# SMC_FrontPanel_ExtensionBoard_Step2_V12_.net
KiCad netlist of a schematic drawn in EAGLE
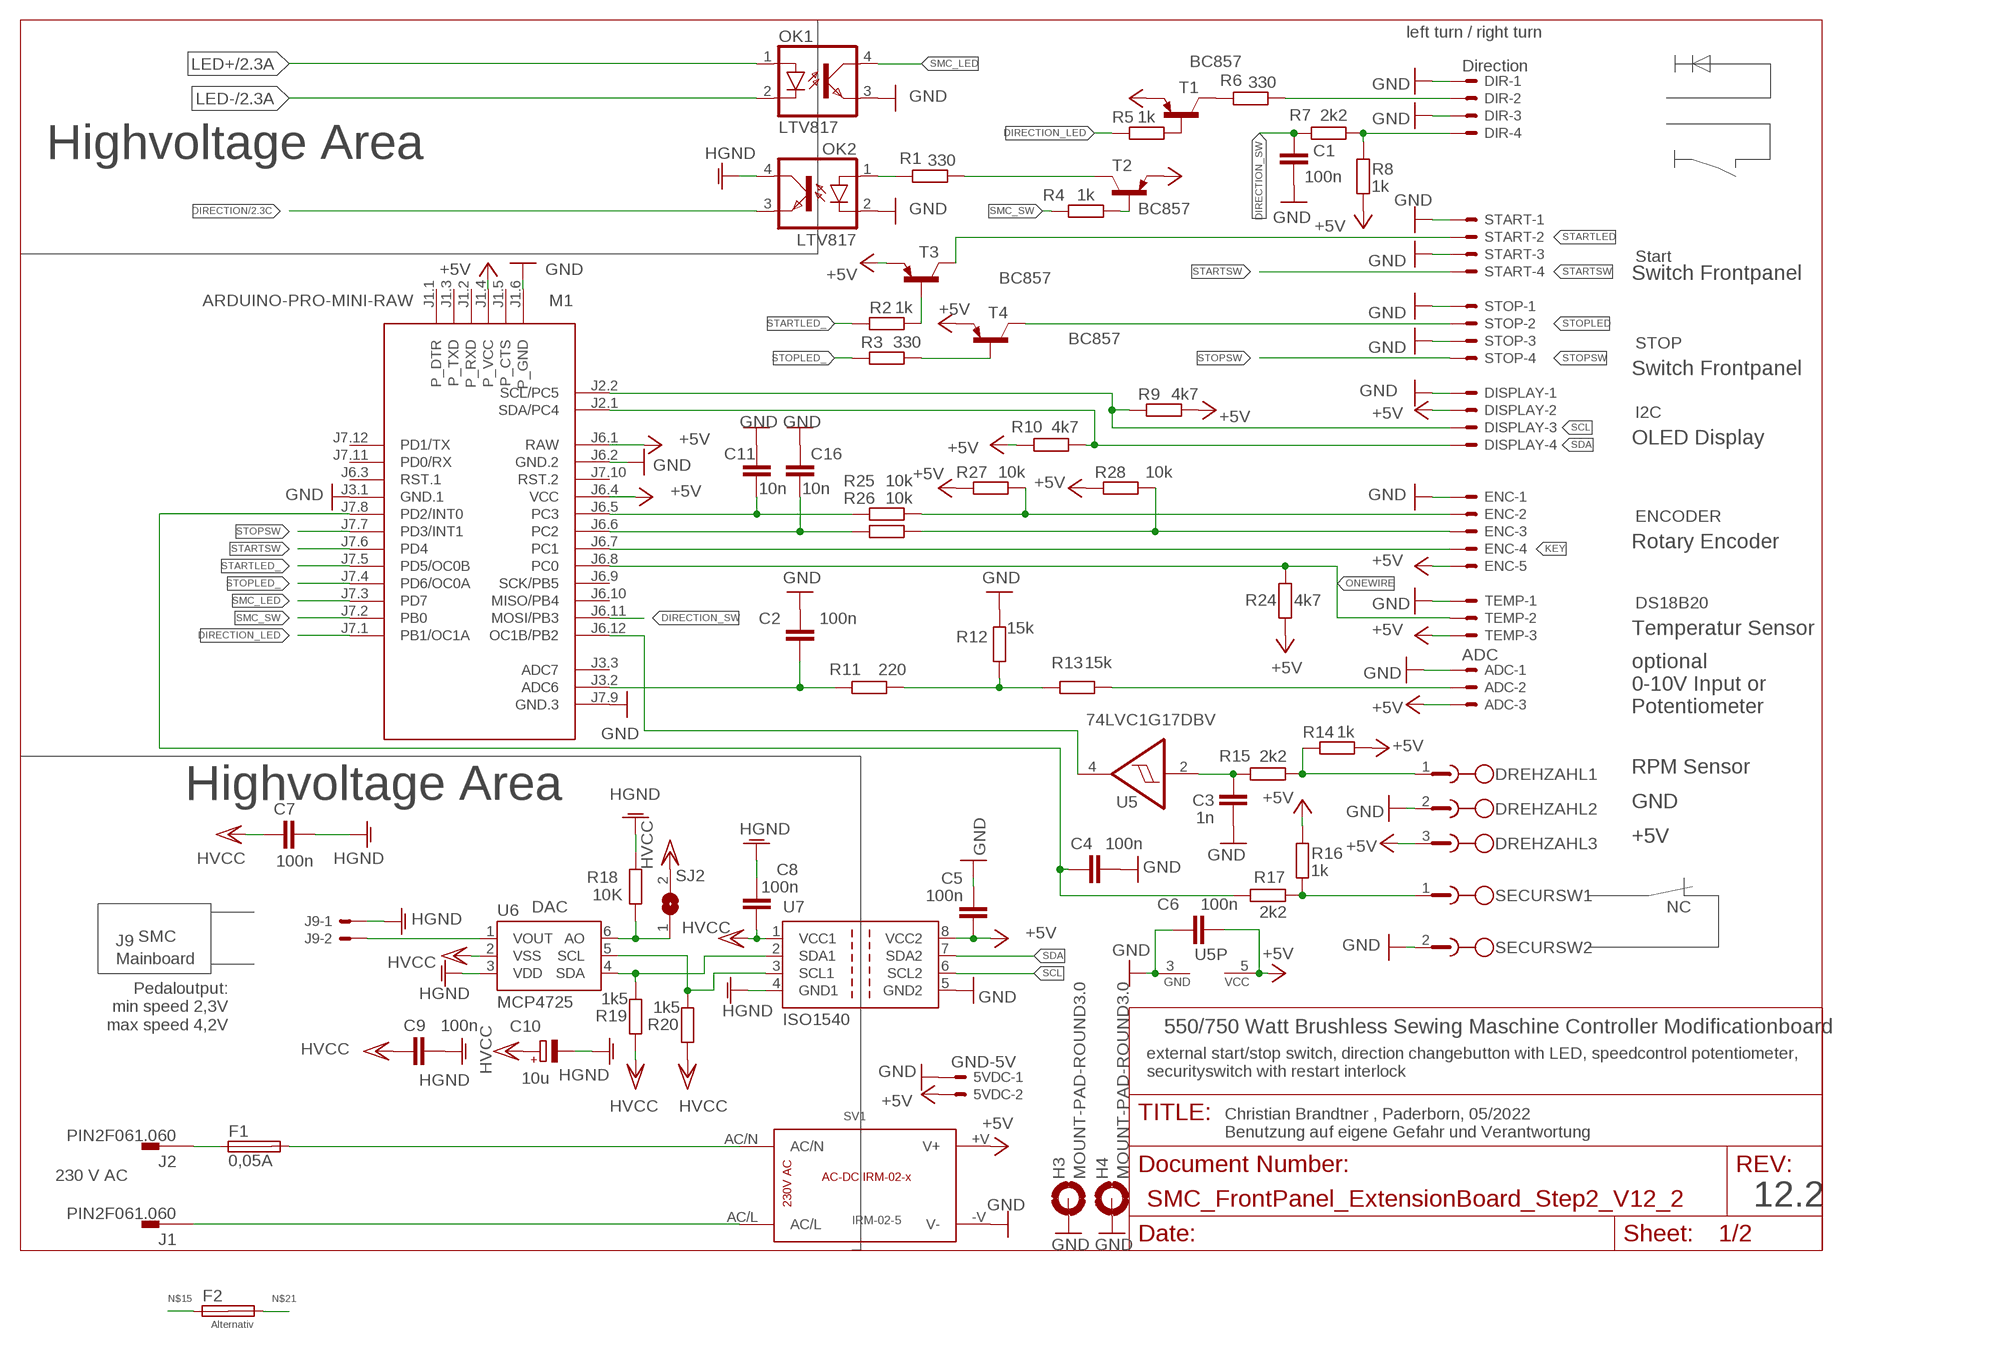
[diagram p0: schematic, sheet 1]
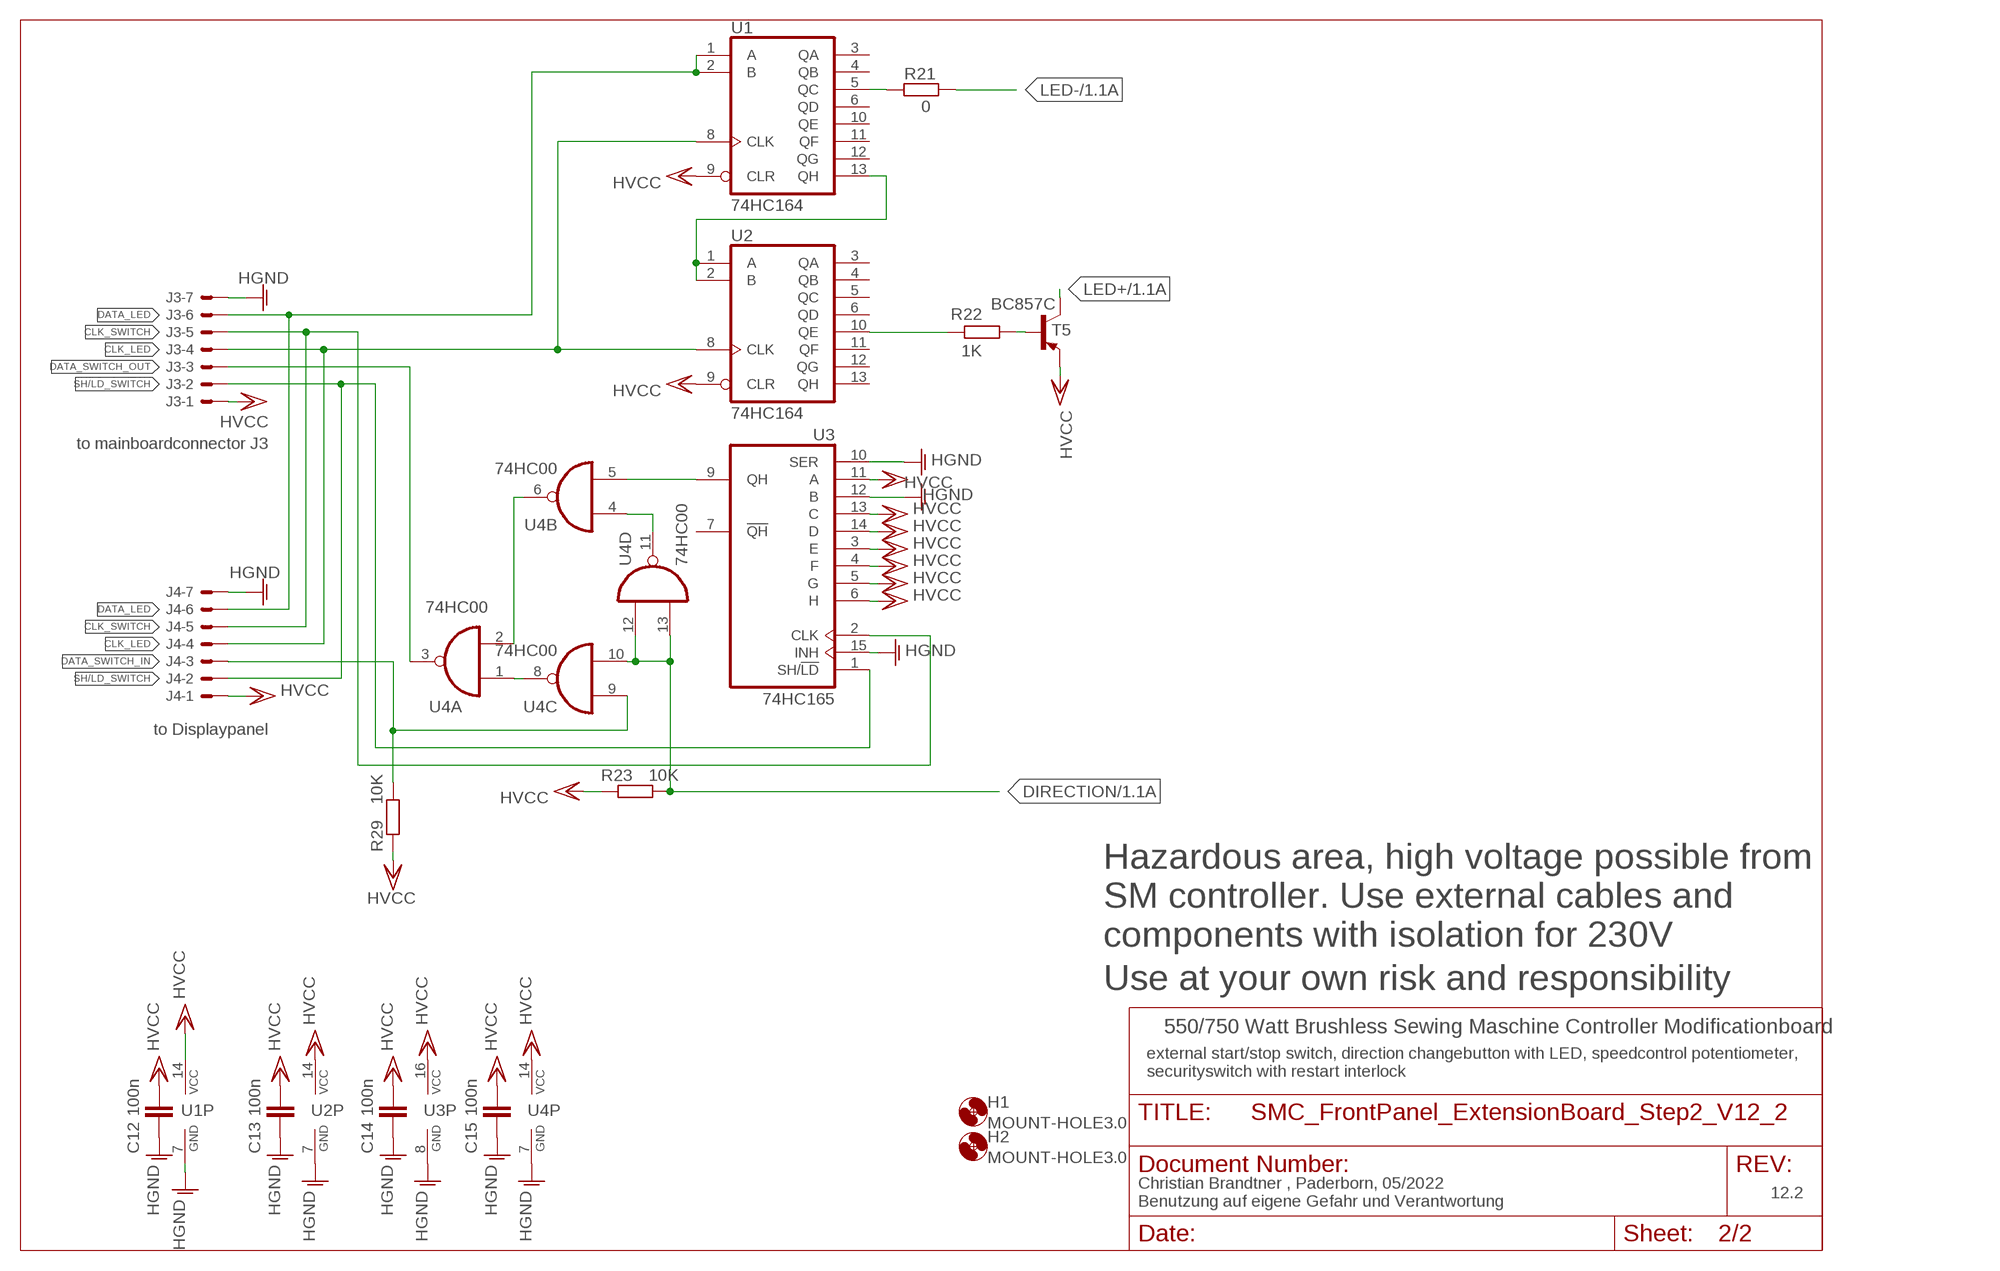
[diagram p1: schematic, sheet 2]

(export (version "E")
  (design (tool "Eeschema 10.0.6"))
  (components
    (comp (ref "C12")
      (value "100n")
      (footprint "eagle-import:C0805")
      (libsource (lib "eagle-import") (part "C-EUC0805"))
    )
    (comp (ref "C13")
      (value "100n")
      (footprint "eagle-import:C0805")
      (libsource (lib "eagle-import") (part "C-EUC0805"))
    )
    (comp (ref "C14")
      (value "100n")
      (footprint "eagle-import:C0805")
      (libsource (lib "eagle-import") (part "C-EUC0805"))
    )
    (comp (ref "C15")
      (value "100n")
      (footprint "eagle-import:C0805")
      (libsource (lib "eagle-import") (part "C-EUC0805"))
    )
    (comp (ref "H1")
      (value "MOUNT-HOLE3.0")
      (footprint "eagle-import:3,0")
      (libsource (lib "eagle-import") (part "MOUNT-HOLE3.0"))
    )
    (comp (ref "H2")
      (value "MOUNT-HOLE3.0")
      (footprint "eagle-import:3,0")
      (libsource (lib "eagle-import") (part "MOUNT-HOLE3.0"))
    )
    (comp (ref "J3")
      (value "to mainboardconnector J3")
      (footprint "eagle-import:JST-XH-07-PACKAGE-ROUND-PAD")
      (libsource (lib "eagle-import") (part "JST-XH-07-PIN-ROUND-PAD"))
    )
    (comp (ref "J4")
      (value "to Displaypanel")
      (footprint "eagle-import:JST-XH-07-PACKAGE-ROUND-PAD")
      (libsource (lib "eagle-import") (part "JST-XH-07-PIN-ROUND-PAD"))
    )
    (comp (ref "R21")
      (value "0")
      (footprint "eagle-import:R0805")
      (libsource (lib "eagle-import") (part "R-EU_R0805"))
    )
    (comp (ref "R22")
      (value "1K")
      (footprint "eagle-import:R0805")
      (libsource (lib "eagle-import") (part "R-EU_R0805"))
    )
    (comp (ref "R23")
      (value "10K")
      (footprint "eagle-import:R0805")
      (libsource (lib "eagle-import") (part "R-EU_R0805"))
    )
    (comp (ref "R29")
      (value "10K")
      (footprint "eagle-import:R0805")
      (libsource (lib "eagle-import") (part "R-EU_R0805"))
    )
    (comp (ref "T5")
      (value "BC857C")
      (footprint "eagle-import:SOT23-BEC")
      (libsource (lib "eagle-import") (part "-PNP-SOT23-BECBC857C"))
    )
    (comp (ref "U1")
      (value "74HC164")
      (footprint "eagle-import:SO14")
      (libsource (lib "eagle-import") (part "74164DHC"))
    )
    (comp (ref "U2")
      (value "74HC164")
      (footprint "eagle-import:SO14")
      (libsource (lib "eagle-import") (part "74164DHC"))
    )
    (comp (ref "U3")
      (value "74HC165")
      (footprint "eagle-import:SO16")
      (libsource (lib "eagle-import") (part "74165DHC"))
    )
    (comp (ref "U4")
      (value "74HC00")
      (footprint "eagle-import:SO14")
      (libsource (lib "eagle-import") (part "7400DHC"))
    )
    (comp (ref "5VDC")
      (value "GND-5V")
      (footprint "eagle-import:JST-XH-02-PACKAGE-ROUND-PAD")
      (libsource (lib "eagle-import") (part "JST-XH-02-PIN-ROUND-PAD"))
    )
    (comp (ref "ADC")
      (value "ADC")
      (footprint "eagle-import:JST-XH-03-PACKAGE-ROUND-PAD")
      (libsource (lib "eagle-import") (part "JST-XH-03-PIN-ROUND-PAD"))
    )
    (comp (ref "C1")
      (value "100n")
      (footprint "eagle-import:C0805")
      (libsource (lib "eagle-import") (part "C-EUC0805"))
    )
    (comp (ref "C2")
      (value "100n")
      (footprint "eagle-import:C0805")
      (libsource (lib "eagle-import") (part "C-EUC0805"))
    )
    (comp (ref "C3")
      (value "1n")
      (footprint "eagle-import:C0805")
      (libsource (lib "eagle-import") (part "C-EUC0805"))
    )
    (comp (ref "C4")
      (value "100n")
      (footprint "eagle-import:C0805")
      (libsource (lib "eagle-import") (part "C-EUC0805"))
    )
    (comp (ref "C5")
      (value "100n")
      (footprint "eagle-import:C0805")
      (libsource (lib "eagle-import") (part "C-EUC0805"))
    )
    (comp (ref "C6")
      (value "100n")
      (footprint "eagle-import:C0805")
      (libsource (lib "eagle-import") (part "C-EUC0805"))
    )
    (comp (ref "C7")
      (value "100n")
      (footprint "eagle-import:C0805")
      (libsource (lib "eagle-import") (part "C-EUC0805"))
    )
    (comp (ref "C8")
      (value "100n")
      (footprint "eagle-import:C0805")
      (libsource (lib "eagle-import") (part "C-EUC0805"))
    )
    (comp (ref "C9")
      (value "100n")
      (footprint "eagle-import:C0805")
      (libsource (lib "eagle-import") (part "C-EUC0805"))
    )
    (comp (ref "C10")
      (value "10u")
      (footprint "eagle-import:153CLV-0405")
      (libsource (lib "eagle-import") (part "CPOL-EU153CLV-0405"))
    )
    (comp (ref "C11")
      (value "10n")
      (footprint "eagle-import:C0805")
      (libsource (lib "eagle-import") (part "C-EUC0805"))
    )
    (comp (ref "C16")
      (value "10n")
      (footprint "eagle-import:C0805")
      (libsource (lib "eagle-import") (part "C-EUC0805"))
    )
    (comp (ref "DIR")
      (value "Direction")
      (footprint "eagle-import:JST-XH-04-PACKAGE-ROUND-PAD")
      (libsource (lib "eagle-import") (part "JST-XH-04-PIN-ROUND-PAD"))
    )
    (comp (ref "DISPLAY")
      (value "I2C")
      (footprint "eagle-import:JST-XH-04-PACKAGE-ROUND-PAD")
      (libsource (lib "eagle-import") (part "JST-XH-04-PIN-ROUND-PAD"))
    )
    (comp (ref "DREHZAHL")
      (value "MCV_1.5/3/-G-3.5")
      (footprint "eagle-import:1843619")
      (libsource (lib "eagle-import") (part "MCV_1.5/3/-G-3.5"))
    )
    (comp (ref "ENC")
      (value "ENCODER")
      (footprint "eagle-import:JST-XH-05-PACKAGE-ROUND-PAD")
      (libsource (lib "eagle-import") (part "JST-XH-05-PIN-ROUND-PAD"))
    )
    (comp (ref "F1")
      (value "0,05A")
      (footprint "eagle-import:MTA501100")
      (libsource (lib "eagle-import") (part "FUSE"))
    )
    (comp (ref "F2")
      (value "SHK20L")
      (footprint "eagle-import:SHK20L")
      (libsource (lib "eagle-import") (part "SHK20L"))
    )
    (comp (ref "H3")
      (value "MOUNT-PAD-ROUND3.0")
      (footprint "eagle-import:3,0-PAD")
      (libsource (lib "eagle-import") (part "MOUNT-PAD-ROUND3.0"))
    )
    (comp (ref "H4")
      (value "MOUNT-PAD-ROUND3.0")
      (footprint "eagle-import:3,0-PAD")
      (libsource (lib "eagle-import") (part "MOUNT-PAD-ROUND3.0"))
    )
    (comp (ref "J1")
      (value "PIN2F061.060")
      (footprint "eagle-import:F061.060")
      (libsource (lib "eagle-import") (part "PIN2F061.060"))
    )
    (comp (ref "J2")
      (value "PIN2F061.060")
      (footprint "eagle-import:F061.060")
      (libsource (lib "eagle-import") (part "PIN2F061.060"))
    )
    (comp (ref "J9")
      (value "JST-XH-02-PIN-ROUND-PAD")
      (footprint "eagle-import:JST-XH-02-PACKAGE-ROUND-PAD")
      (libsource (lib "eagle-import") (part "JST-XH-02-PIN-ROUND-PAD"))
    )
    (comp (ref "M1")
      (value "ARDUINO-PRO-MINI-RAW")
      (footprint "eagle-import:ARDUINO-PRO-MINI")
      (libsource (lib "eagle-import") (part "ARDUINO-PRO-MINI-RAW"))
    )
    (comp (ref "OK1")
      (value "LTV817")
      (footprint "eagle-import:SMD4-7")
      (fields (field (name "MF") "VISHAY/TELEFUNKEN") (field (name "MPN") "SFH6186-2"))
      (libsource (lib "eagle-import") (part "SFH618?6-2"))
    )
    (comp (ref "OK2")
      (value "LTV817")
      (footprint "eagle-import:SMD4-7")
      (fields (field (name "MF") "VISHAY/TELEFUNKEN") (field (name "MPN") "SFH6186-2"))
      (libsource (lib "eagle-import") (part "SFH618?6-2"))
    )
    (comp (ref "R1")
      (value "330")
      (footprint "eagle-import:R0805")
      (libsource (lib "eagle-import") (part "R-EU_R0805"))
    )
    (comp (ref "R2")
      (value "1k")
      (footprint "eagle-import:R0805")
      (libsource (lib "eagle-import") (part "R-EU_R0805"))
    )
    (comp (ref "R3")
      (value "330")
      (footprint "eagle-import:R0805")
      (libsource (lib "eagle-import") (part "R-EU_R0805"))
    )
    (comp (ref "R4")
      (value "1k")
      (footprint "eagle-import:R0805")
      (libsource (lib "eagle-import") (part "R-EU_R0805"))
    )
    (comp (ref "R5")
      (value "1k")
      (footprint "eagle-import:R0805")
      (libsource (lib "eagle-import") (part "R-EU_R0805"))
    )
    (comp (ref "R6")
      (value "330")
      (footprint "eagle-import:R0805")
      (libsource (lib "eagle-import") (part "R-EU_R0805"))
    )
    (comp (ref "R7")
      (value "2k2")
      (footprint "eagle-import:R0805")
      (libsource (lib "eagle-import") (part "R-EU_R0805"))
    )
    (comp (ref "R8")
      (value "1k")
      (footprint "eagle-import:R0805")
      (libsource (lib "eagle-import") (part "R-EU_R0805"))
    )
    (comp (ref "R9")
      (value "4k7")
      (footprint "eagle-import:R0805")
      (libsource (lib "eagle-import") (part "R-EU_R0805"))
    )
    (comp (ref "R10")
      (value "4k7")
      (footprint "eagle-import:R0805")
      (libsource (lib "eagle-import") (part "R-EU_R0805"))
    )
    (comp (ref "R11")
      (value "220")
      (footprint "eagle-import:R0805")
      (libsource (lib "eagle-import") (part "R-EU_R0805"))
    )
    (comp (ref "R12")
      (value "15k")
      (footprint "eagle-import:R0805")
      (libsource (lib "eagle-import") (part "R-EU_R0805"))
    )
    (comp (ref "R13")
      (value "15k")
      (footprint "eagle-import:R0805")
      (libsource (lib "eagle-import") (part "R-EU_R0805"))
    )
    (comp (ref "R14")
      (value "1k")
      (footprint "eagle-import:R0805")
      (libsource (lib "eagle-import") (part "R-EU_R0805"))
    )
    (comp (ref "R15")
      (value "2k2")
      (footprint "eagle-import:R0805")
      (libsource (lib "eagle-import") (part "R-EU_R0805"))
    )
    (comp (ref "R16")
      (value "1k")
      (footprint "eagle-import:R0805")
      (libsource (lib "eagle-import") (part "R-EU_R0805"))
    )
    (comp (ref "R17")
      (value "2k2")
      (footprint "eagle-import:R0805")
      (libsource (lib "eagle-import") (part "R-EU_R0805"))
    )
    (comp (ref "R18")
      (value "10K")
      (footprint "eagle-import:R0805")
      (libsource (lib "eagle-import") (part "R-EU_R0805"))
    )
    (comp (ref "R19")
      (value "1k5")
      (footprint "eagle-import:R0805")
      (libsource (lib "eagle-import") (part "R-EU_R0805"))
    )
    (comp (ref "R20")
      (value "1k5")
      (footprint "eagle-import:R0805")
      (libsource (lib "eagle-import") (part "R-EU_R0805"))
    )
    (comp (ref "R24")
      (value "4k7")
      (footprint "eagle-import:R0805")
      (libsource (lib "eagle-import") (part "R-EU_R0805"))
    )
    (comp (ref "R25")
      (value "10k")
      (footprint "eagle-import:R0805")
      (libsource (lib "eagle-import") (part "R-EU_R0805"))
    )
    (comp (ref "R26")
      (value "10k")
      (footprint "eagle-import:R0805")
      (libsource (lib "eagle-import") (part "R-EU_R0805"))
    )
    (comp (ref "R27")
      (value "10k")
      (footprint "eagle-import:R0805")
      (libsource (lib "eagle-import") (part "R-EU_R0805"))
    )
    (comp (ref "R28")
      (value "10k")
      (footprint "eagle-import:R0805")
      (libsource (lib "eagle-import") (part "R-EU_R0805"))
    )
    (comp (ref "SECURSW")
      (value "MCV_1,5/2-G-3,5")
      (footprint "eagle-import:1843606")
      (libsource (lib "eagle-import") (part "MCV_1,5/2-G-3,5"))
    )
    (comp (ref "SJ2") (value "SJ") (footprint "eagle-import:SJ") (libsource (lib "eagle-import") (part "SJ")))
    (comp (ref "START")
      (value "Start")
      (footprint "eagle-import:JST-XH-04-PACKAGE-ROUND-PAD")
      (libsource (lib "eagle-import") (part "JST-XH-04-PIN-ROUND-PAD"))
    )
    (comp (ref "STOP")
      (value "STOP")
      (footprint "eagle-import:JST-XH-04-PACKAGE-ROUND-PAD")
      (libsource (lib "eagle-import") (part "JST-XH-04-PIN-ROUND-PAD"))
    )
    (comp (ref "SV1")
      (value "IRM-02-5")
      (footprint "eagle-import:IRM-02-X")
      (libsource (lib "eagle-import") (part "IRM-02-X"))
    )
    (comp (ref "T1")
      (value "BC857")
      (footprint "eagle-import:SOT23-BEC")
      (libsource (lib "eagle-import") (part "BC857SMDA"))
    )
    (comp (ref "T2")
      (value "BC857")
      (footprint "eagle-import:SOT23-BEC")
      (libsource (lib "eagle-import") (part "BC857SMDA"))
    )
    (comp (ref "T3")
      (value "BC857")
      (footprint "eagle-import:SOT23-BEC")
      (libsource (lib "eagle-import") (part "BC857SMDA"))
    )
    (comp (ref "T4")
      (value "BC857")
      (footprint "eagle-import:SOT23-BEC")
      (libsource (lib "eagle-import") (part "BC857SMDA"))
    )
    (comp (ref "TEMP")
      (value "DS18B20")
      (footprint "eagle-import:JST-XH-03-PACKAGE-ROUND-PAD")
      (libsource (lib "eagle-import") (part "JST-XH-03-PIN-ROUND-PAD"))
    )
    (comp (ref "U5")
      (value "74LVC1G17DBV")
      (footprint "eagle-import:SOT23-5")
      (libsource (lib "eagle-import") (part "741G17DBVLVC"))
    )
    (comp (ref "U6")
      (value "MCP4725")
      (footprint "eagle-import:SOT23-6")
      (libsource (lib "eagle-import") (part "MCP4725SOT-23"))
    )
    (comp (ref "U7")
      (value "ISO1540")
      (footprint "eagle-import:SO-08")
      (libsource (lib "eagle-import") (part "ISO1540"))
    )
  )
  (nets
    (net (code "1") (name "+5V") (class "Default")
      (node (ref "5VDC") (pin "2") (pinfunction "S_2") (pintype "passive"))
      (node (ref "ADC") (pin "3") (pinfunction "S_3") (pintype "passive"))
      (node (ref "C5") (pin "1") (pinfunction "1_1") (pintype "passive"))
      (node (ref "C6") (pin "1") (pinfunction "1_1") (pintype "passive"))
      (node (ref "DISPLAY") (pin "2") (pinfunction "S_2") (pintype "passive"))
      (node (ref "DREHZAHL") (pin "3") (pinfunction "1_3") (pintype "passive"))
      (node (ref "ENC") (pin "5") (pinfunction "S_5") (pintype "passive"))
      (node (ref "M1") (pin "J1.4") (pinfunction "P_VCC_J1.4") (pintype "bidirectional"))
      (node (ref "M1") (pin "J6.1") (pinfunction "RAW_J6.1") (pintype "power_in"))
      (node (ref "M1") (pin "J6.4") (pinfunction "VCC_J6.4") (pintype "power_in"))
      (node (ref "R10") (pin "1") (pinfunction "1_1") (pintype "passive"))
      (node (ref "R14") (pin "1") (pinfunction "1_1") (pintype "passive"))
      (node (ref "R16") (pin "1") (pinfunction "1_1") (pintype "passive"))
      (node (ref "R24") (pin "2") (pinfunction "2_2") (pintype "passive"))
      (node (ref "R27") (pin "1") (pinfunction "1_1") (pintype "passive"))
      (node (ref "R28") (pin "1") (pinfunction "1_1") (pintype "passive"))
      (node (ref "R8") (pin "2") (pinfunction "2_2") (pintype "passive"))
      (node (ref "R9") (pin "1") (pinfunction "1_1") (pintype "passive"))
      (node (ref "SV1") (pin "+V") (pinfunction "V+_+V") (pintype "bidirectional"))
      (node (ref "T1") (pin "E") (pinfunction "E_E") (pintype "passive"))
      (node (ref "T2") (pin "E") (pinfunction "E_E") (pintype "passive"))
      (node (ref "T3") (pin "E") (pinfunction "E_E") (pintype "passive"))
      (node (ref "T4") (pin "E") (pinfunction "E_E") (pintype "passive"))
      (node (ref "TEMP") (pin "3") (pinfunction "S_3") (pintype "passive"))
      (node (ref "U5") (pin "5") (pinfunction "VCC_5") (pintype "power_in"))
      (node (ref "U7") (pin "8") (pinfunction "VCC2_8") (pintype "power_in"))
    )
    (net (code "2") (name "CLK_LED") (class "Default")
      (node (ref "J3") (pin "4") (pinfunction "S_4") (pintype "passive"))
      (node (ref "J4") (pin "4") (pinfunction "S_4") (pintype "passive"))
      (node (ref "U1") (pin "8") (pinfunction "CLK_8") (pintype "input"))
      (node (ref "U2") (pin "8") (pinfunction "CLK_8") (pintype "input"))
    )
    (net (code "3") (name "CLK_SWITCH") (class "Default")
      (node (ref "J3") (pin "5") (pinfunction "S_5") (pintype "passive"))
      (node (ref "J4") (pin "5") (pinfunction "S_5") (pintype "passive"))
      (node (ref "U3") (pin "2") (pinfunction "CLK_2") (pintype "input"))
    )
    (net (code "4") (name "DATA_LED") (class "Default")
      (node (ref "J3") (pin "6") (pinfunction "S_6") (pintype "passive"))
      (node (ref "J4") (pin "6") (pinfunction "S_6") (pintype "passive"))
      (node (ref "U1") (pin "1") (pinfunction "A_1") (pintype "input"))
      (node (ref "U1") (pin "2") (pinfunction "B_2") (pintype "input"))
    )
    (net (code "5") (name "DATA_SWITCH_IN") (class "Default")
      (node (ref "J4") (pin "3") (pinfunction "S_3") (pintype "passive"))
      (node (ref "R29") (pin "1") (pinfunction "1_1") (pintype "passive"))
      (node (ref "U4") (pin "9") (pinfunction "I0_9") (pintype "input"))
    )
    (net (code "6") (name "DATA_SWITCH_OUT") (class "Default")
      (node (ref "J3") (pin "3") (pinfunction "S_3") (pintype "passive"))
      (node (ref "U4") (pin "3") (pinfunction "O_3") (pintype "output"))
    )
    (net (code "7") (name "DIRECTION") (class "Default")
      (node (ref "OK2") (pin "3") (pinfunction "EMIT_3") (pintype "passive"))
      (node (ref "R23") (pin "1") (pinfunction "1_1") (pintype "passive"))
      (node (ref "U4") (pin "10") (pinfunction "I1_10") (pintype "input"))
      (node (ref "U4") (pin "12") (pinfunction "I0_12") (pintype "input"))
      (node (ref "U4") (pin "13") (pinfunction "I1_13") (pintype "input"))
    )
    (net (code "8") (name "DIRECTION_LED") (class "Default")
      (node (ref "M1") (pin "J7.1") (pinfunction "PB1/OC1A_J7.1") (pintype "bidirectional"))
      (node (ref "R5") (pin "2") (pinfunction "2_2") (pintype "passive"))
    )
    (net (code "9") (name "DIRECTION_SW") (class "Default")
      (node (ref "C1") (pin "2") (pinfunction "2_2") (pintype "passive"))
      (node (ref "M1") (pin "J6.11") (pinfunction "MOSI/PB3_J6.11") (pintype "bidirectional"))
      (node (ref "R7") (pin "1") (pinfunction "1_1") (pintype "passive"))
    )
    (net (code "10") (name "GND") (class "Default")
      (node (ref "5VDC") (pin "1") (pinfunction "S_1") (pintype "passive"))
      (node (ref "ADC") (pin "1") (pinfunction "S_1") (pintype "passive"))
      (node (ref "C1") (pin "1") (pinfunction "1_1") (pintype "passive"))
      (node (ref "C11") (pin "2") (pinfunction "2_2") (pintype "passive"))
      (node (ref "C16") (pin "2") (pinfunction "2_2") (pintype "passive"))
      (node (ref "C2") (pin "2") (pinfunction "2_2") (pintype "passive"))
      (node (ref "C3") (pin "1") (pinfunction "1_1") (pintype "passive"))
      (node (ref "C4") (pin "2") (pinfunction "2_2") (pintype "passive"))
      (node (ref "C5") (pin "2") (pinfunction "2_2") (pintype "passive"))
      (node (ref "C6") (pin "2") (pinfunction "2_2") (pintype "passive"))
      (node (ref "DIR") (pin "1") (pinfunction "S_1") (pintype "passive"))
      (node (ref "DIR") (pin "3") (pinfunction "S_3") (pintype "passive"))
      (node (ref "DISPLAY") (pin "1") (pinfunction "S_1") (pintype "passive"))
      (node (ref "DREHZAHL") (pin "2") (pinfunction "1_2") (pintype "passive"))
      (node (ref "ENC") (pin "1") (pinfunction "S_1") (pintype "passive"))
      (node (ref "H3") (pin "B3,0") (pinfunction "MOUNT_B3,0") (pintype "passive"))
      (node (ref "H4") (pin "B3,0") (pinfunction "MOUNT_B3,0") (pintype "passive"))
      (node (ref "M1") (pin "J1.6") (pinfunction "P_GND_J1.6") (pintype "bidirectional"))
      (node (ref "M1") (pin "J3.1") (pinfunction "GND.1_J3.1") (pintype "power_in"))
      (node (ref "M1") (pin "J6.2") (pinfunction "GND.2_J6.2") (pintype "power_in"))
      (node (ref "M1") (pin "J7.9") (pinfunction "GND.3_J7.9") (pintype "bidirectional"))
      (node (ref "OK1") (pin "3") (pinfunction "EMIT_3") (pintype "passive"))
      (node (ref "OK2") (pin "2") (pinfunction "C_2") (pintype "passive"))
      (node (ref "R12") (pin "2") (pinfunction "2_2") (pintype "passive"))
      (node (ref "SECURSW") (pin "2") (pinfunction "1_2") (pintype "passive"))
      (node (ref "START") (pin "1") (pinfunction "S_1") (pintype "passive"))
      (node (ref "START") (pin "3") (pinfunction "S_3") (pintype "passive"))
      (node (ref "STOP") (pin "1") (pinfunction "S_1") (pintype "passive"))
      (node (ref "STOP") (pin "3") (pinfunction "S_3") (pintype "passive"))
      (node (ref "SV1") (pin "-V") (pinfunction "V-_-V") (pintype "bidirectional"))
      (node (ref "TEMP") (pin "1") (pinfunction "S_1") (pintype "passive"))
      (node (ref "U5") (pin "3") (pinfunction "GND_3") (pintype "power_in"))
      (node (ref "U7") (pin "5") (pinfunction "GND2_5") (pintype "power_in"))
    )
    (net (code "11") (name "HGND") (class "Default")
      (node (ref "C10") (pin "-") (pinfunction "-_-") (pintype "passive"))
      (node (ref "C12") (pin "1") (pinfunction "1_1") (pintype "passive"))
      (node (ref "C13") (pin "1") (pinfunction "1_1") (pintype "passive"))
      (node (ref "C14") (pin "1") (pinfunction "1_1") (pintype "passive"))
      (node (ref "C15") (pin "1") (pinfunction "1_1") (pintype "passive"))
      (node (ref "C7") (pin "1") (pinfunction "1_1") (pintype "passive"))
      (node (ref "C8") (pin "2") (pinfunction "2_2") (pintype "passive"))
      (node (ref "C9") (pin "1") (pinfunction "1_1") (pintype "passive"))
      (node (ref "J3") (pin "7") (pinfunction "S_7") (pintype "passive"))
      (node (ref "J4") (pin "7") (pinfunction "S_7") (pintype "passive"))
      (node (ref "J9") (pin "1") (pinfunction "S_1") (pintype "passive"))
      (node (ref "OK2") (pin "4") (pinfunction "COL_4") (pintype "passive"))
      (node (ref "R18") (pin "1") (pinfunction "1_1") (pintype "passive"))
      (node (ref "U1") (pin "7") (pinfunction "GND_7") (pintype "power_in"))
      (node (ref "U2") (pin "7") (pinfunction "GND_7") (pintype "power_in"))
      (node (ref "U3") (pin "10") (pinfunction "SER_10") (pintype "input"))
      (node (ref "U3") (pin "12") (pinfunction "B_12") (pintype "input"))
      (node (ref "U3") (pin "15") (pinfunction "INH_15") (pintype "input"))
      (node (ref "U3") (pin "8") (pinfunction "GND_8") (pintype "power_in"))
      (node (ref "U4") (pin "7") (pinfunction "GND_7") (pintype "power_in"))
      (node (ref "U6") (pin "3") (pinfunction "VDD_3") (pintype "bidirectional"))
      (node (ref "U7") (pin "4") (pinfunction "GND1_4") (pintype "power_in"))
    )
    (net (code "12") (name "HVCC") (class "Default")
      (node (ref "C10") (pin "+") (pinfunction "+_+") (pintype "passive"))
      (node (ref "C12") (pin "2") (pinfunction "2_2") (pintype "passive"))
      (node (ref "C13") (pin "2") (pinfunction "2_2") (pintype "passive"))
      (node (ref "C14") (pin "2") (pinfunction "2_2") (pintype "passive"))
      (node (ref "C15") (pin "2") (pinfunction "2_2") (pintype "passive"))
      (node (ref "C7") (pin "2") (pinfunction "2_2") (pintype "passive"))
      (node (ref "C8") (pin "1") (pinfunction "1_1") (pintype "passive"))
      (node (ref "C9") (pin "2") (pinfunction "2_2") (pintype "passive"))
      (node (ref "J3") (pin "1") (pinfunction "S_1") (pintype "passive"))
      (node (ref "J4") (pin "1") (pinfunction "S_1") (pintype "passive"))
      (node (ref "R19") (pin "2") (pinfunction "2_2") (pintype "passive"))
      (node (ref "R20") (pin "2") (pinfunction "2_2") (pintype "passive"))
      (node (ref "R23") (pin "2") (pinfunction "2_2") (pintype "passive"))
      (node (ref "R29") (pin "2") (pinfunction "2_2") (pintype "passive"))
      (node (ref "SJ2") (pin "2") (pinfunction "2_2") (pintype "passive"))
      (node (ref "T5") (pin "E") (pinfunction "E_E") (pintype "passive"))
      (node (ref "U1") (pin "14") (pinfunction "VCC_14") (pintype "power_in"))
      (node (ref "U1") (pin "9") (pinfunction "CLR_9") (pintype "input"))
      (node (ref "U2") (pin "14") (pinfunction "VCC_14") (pintype "power_in"))
      (node (ref "U2") (pin "9") (pinfunction "CLR_9") (pintype "input"))
      (node (ref "U3") (pin "11") (pinfunction "A_11") (pintype "input"))
      (node (ref "U3") (pin "13") (pinfunction "C_13") (pintype "input"))
      (node (ref "U3") (pin "14") (pinfunction "D_14") (pintype "input"))
      (node (ref "U3") (pin "16") (pinfunction "VCC_16") (pintype "power_in"))
      (node (ref "U3") (pin "3") (pinfunction "E_3") (pintype "input"))
      (node (ref "U3") (pin "4") (pinfunction "F_4") (pintype "input"))
      (node (ref "U3") (pin "5") (pinfunction "G_5") (pintype "input"))
      (node (ref "U3") (pin "6") (pinfunction "H_6") (pintype "input"))
      (node (ref "U4") (pin "14") (pinfunction "VCC_14") (pintype "power_in"))
      (node (ref "U6") (pin "2") (pinfunction "VSS_2") (pintype "bidirectional"))
      (node (ref "U7") (pin "1") (pinfunction "VCC1_1") (pintype "power_in"))
    )
    (net (code "13") (name "KEY") (class "Default")
      (node (ref "ENC") (pin "4") (pinfunction "S_4") (pintype "passive"))
      (node (ref "M1") (pin "J6.7") (pinfunction "PC1_J6.7") (pintype "bidirectional"))
    )
    (net (code "14") (name "LED+") (class "Default")
      (node (ref "OK1") (pin "1") (pinfunction "A_1") (pintype "passive"))
      (node (ref "T5") (pin "C") (pinfunction "C_C") (pintype "passive"))
    )
    (net (code "15") (name "LED-") (class "Default")
      (node (ref "OK1") (pin "2") (pinfunction "C_2") (pintype "passive"))
      (node (ref "R21") (pin "2") (pinfunction "2_2") (pintype "passive"))
    )
    (net (code "16") (name "N$15") (class "Default")
      (node (ref "F1") (pin "1") (pinfunction "1_1") (pintype "passive"))
      (node (ref "F2") (pin "1A") (pinfunction "1A_1A") (pintype "passive"))
      (node (ref "J2") (pin "A1") (pinfunction "1_A1") (pintype "passive"))
      (node (ref "J2") (pin "A2") (pinfunction "1_A2") (pintype "passive"))
    )
    (net (code "17") (name "N$21") (class "Default")
      (node (ref "F1") (pin "2") (pinfunction "2_2") (pintype "passive"))
      (node (ref "F2") (pin "2A") (pinfunction "2A_2A") (pintype "passive"))
      (node (ref "SV1") (pin "AC/N") (pinfunction "AC/N_AC/N") (pintype "bidirectional"))
    )
    (net (code "18") (name "Net-(ADCB-S)") (class "Default")
      (node (ref "ADC") (pin "2") (pinfunction "S_2") (pintype "passive"))
      (node (ref "R13") (pin "1") (pinfunction "1_1") (pintype "passive"))
    )
    (net (code "19") (name "Net-(DIRB-S)") (class "Default")
      (node (ref "DIR") (pin "2") (pinfunction "S_2") (pintype "passive"))
      (node (ref "R6") (pin "1") (pinfunction "1_1") (pintype "passive"))
    )
    (net (code "20") (name "Net-(DIRD-S)") (class "Default")
      (node (ref "DIR") (pin "4") (pinfunction "S_4") (pintype "passive"))
      (node (ref "R7") (pin "2") (pinfunction "2_2") (pintype "passive"))
      (node (ref "R8") (pin "1") (pinfunction "1_1") (pintype "passive"))
    )
    (net (code "21") (name "Net-(DREHZAHL-Pad1)") (class "Default")
      (node (ref "DREHZAHL") (pin "1") (pinfunction "1_1") (pintype "passive"))
      (node (ref "R14") (pin "2") (pinfunction "2_2") (pintype "passive"))
      (node (ref "R15") (pin "2") (pinfunction "2_2") (pintype "passive"))
    )
    (net (code "22") (name "Net-(ENCB-S)") (class "Default")
      (node (ref "ENC") (pin "2") (pinfunction "S_2") (pintype "passive"))
      (node (ref "R25") (pin "2") (pinfunction "2_2") (pintype "passive"))
      (node (ref "R27") (pin "2") (pinfunction "2_2") (pintype "passive"))
    )
    (net (code "23") (name "Net-(ENCC-S)") (class "Default")
      (node (ref "ENC") (pin "3") (pinfunction "S_3") (pintype "passive"))
      (node (ref "R26") (pin "2") (pinfunction "2_2") (pintype "passive"))
      (node (ref "R28") (pin "2") (pinfunction "2_2") (pintype "passive"))
    )
    (net (code "24") (name "Net-(J1-1-PadA1)") (class "Default")
      (node (ref "J1") (pin "A1") (pinfunction "1_A1") (pintype "passive"))
      (node (ref "J1") (pin "A2") (pinfunction "1_A2") (pintype "passive"))
      (node (ref "SV1") (pin "AC/L") (pinfunction "AC/L_AC/L") (pintype "bidirectional"))
    )
    (net (code "25") (name "Net-(J9B-S)") (class "Default")
      (node (ref "J9") (pin "2") (pinfunction "S_2") (pintype "passive"))
      (node (ref "U6") (pin "1") (pinfunction "VOUT_1") (pintype "bidirectional"))
    )
    (net (code "26") (name "Net-(M1-ADC6)") (class "Default")
      (node (ref "C2") (pin "1") (pinfunction "1_1") (pintype "passive"))
      (node (ref "M1") (pin "J3.2") (pinfunction "ADC6_J3.2") (pintype "bidirectional"))
      (node (ref "R11") (pin "1") (pinfunction "1_1") (pintype "passive"))
    )
    (net (code "27") (name "Net-(M1-OC1B{slash}PB2)") (class "Default")
      (node (ref "M1") (pin "J6.12") (pinfunction "OC1B/PB2_J6.12") (pintype "bidirectional"))
      (node (ref "U5") (pin "4") (pinfunction "O_4") (pintype "output"))
    )
    (net (code "28") (name "Net-(M1-PC2)") (class "Default")
      (node (ref "C16") (pin "1") (pinfunction "1_1") (pintype "passive"))
      (node (ref "M1") (pin "J6.6") (pinfunction "PC2_J6.6") (pintype "bidirectional"))
      (node (ref "R26") (pin "1") (pinfunction "1_1") (pintype "passive"))
    )
    (net (code "29") (name "Net-(M1-PC3)") (class "Default")
      (node (ref "C11") (pin "1") (pinfunction "1_1") (pintype "passive"))
      (node (ref "M1") (pin "J6.5") (pinfunction "PC3_J6.5") (pintype "bidirectional"))
      (node (ref "R25") (pin "1") (pinfunction "1_1") (pintype "passive"))
    )
    (net (code "30") (name "Net-(M1-PD2{slash}INT0)") (class "Default")
      (node (ref "C4") (pin "1") (pinfunction "1_1") (pintype "passive"))
      (node (ref "M1") (pin "J7.8") (pinfunction "PD2/INT0_J7.8") (pintype "bidirectional"))
      (node (ref "R17") (pin "1") (pinfunction "1_1") (pintype "passive"))
    )
    (net (code "31") (name "Net-(OK2-A)") (class "Default")
      (node (ref "OK2") (pin "1") (pinfunction "A_1") (pintype "passive"))
      (node (ref "R1") (pin "2") (pinfunction "2_2") (pintype "passive"))
    )
    (net (code "32") (name "Net-(R1-Pad1)") (class "Default")
      (node (ref "R1") (pin "1") (pinfunction "1_1") (pintype "passive"))
      (node (ref "T2") (pin "C") (pinfunction "C_C") (pintype "passive"))
    )
    (net (code "33") (name "Net-(R2-Pad1)") (class "Default")
      (node (ref "R2") (pin "1") (pinfunction "1_1") (pintype "passive"))
      (node (ref "T3") (pin "B") (pinfunction "B_B") (pintype "passive"))
    )
    (net (code "34") (name "Net-(R3-Pad1)") (class "Default")
      (node (ref "R3") (pin "1") (pinfunction "1_1") (pintype "passive"))
      (node (ref "T4") (pin "B") (pinfunction "B_B") (pintype "passive"))
    )
    (net (code "35") (name "Net-(R4-Pad1)") (class "Default")
      (node (ref "R4") (pin "1") (pinfunction "1_1") (pintype "passive"))
      (node (ref "T2") (pin "B") (pinfunction "B_B") (pintype "passive"))
    )
    (net (code "36") (name "Net-(R5-Pad1)") (class "Default")
      (node (ref "R5") (pin "1") (pinfunction "1_1") (pintype "passive"))
      (node (ref "T1") (pin "B") (pinfunction "B_B") (pintype "passive"))
    )
    (net (code "37") (name "Net-(R6-Pad2)") (class "Default")
      (node (ref "R6") (pin "2") (pinfunction "2_2") (pintype "passive"))
      (node (ref "T1") (pin "C") (pinfunction "C_C") (pintype "passive"))
    )
    (net (code "38") (name "Net-(R11-Pad2)") (class "Default")
      (node (ref "R11") (pin "2") (pinfunction "2_2") (pintype "passive"))
      (node (ref "R12") (pin "1") (pinfunction "1_1") (pintype "passive"))
      (node (ref "R13") (pin "2") (pinfunction "2_2") (pintype "passive"))
    )
    (net (code "39") (name "Net-(R16-Pad2)") (class "Default")
      (node (ref "R16") (pin "2") (pinfunction "2_2") (pintype "passive"))
      (node (ref "R17") (pin "2") (pinfunction "2_2") (pintype "passive"))
      (node (ref "SECURSW") (pin "1") (pinfunction "1_1") (pintype "passive"))
    )
    (net (code "40") (name "Net-(R22-Pad1)") (class "Default")
      (node (ref "R22") (pin "1") (pinfunction "1_1") (pintype "passive"))
      (node (ref "T5") (pin "B") (pinfunction "B_B") (pintype "passive"))
    )
    (net (code "41") (name "Net-(U1A-QC)") (class "Default")
      (node (ref "R21") (pin "1") (pinfunction "1_1") (pintype "passive"))
      (node (ref "U1") (pin "5") (pinfunction "QC_5") (pintype "output"))
    )
    (net (code "42") (name "Net-(U1A-QH)") (class "Default")
      (node (ref "U1") (pin "13") (pinfunction "QH_13") (pintype "output"))
      (node (ref "U2") (pin "1") (pinfunction "A_1") (pintype "input"))
      (node (ref "U2") (pin "2") (pinfunction "B_2") (pintype "input"))
    )
    (net (code "43") (name "Net-(U2A-QE)") (class "Default")
      (node (ref "R22") (pin "2") (pinfunction "2_2") (pintype "passive"))
      (node (ref "U2") (pin "10") (pinfunction "QE_10") (pintype "output"))
    )
    (net (code "44") (name "Net-(U3A-QH)") (class "Default")
      (node (ref "U3") (pin "9") (pinfunction "QH_9") (pintype "output"))
      (node (ref "U4") (pin "5") (pinfunction "I1_5") (pintype "input"))
    )
    (net (code "45") (name "Net-(U4A-I0)") (class "Default")
      (node (ref "U4") (pin "1") (pinfunction "I0_1") (pintype "input"))
      (node (ref "U4") (pin "8") (pinfunction "O_8") (pintype "output"))
    )
    (net (code "46") (name "Net-(U4A-I1)") (class "Default")
      (node (ref "U4") (pin "2") (pinfunction "I1_2") (pintype "input"))
      (node (ref "U4") (pin "6") (pinfunction "O_6") (pintype "output"))
    )
    (net (code "47") (name "Net-(U4B-I0)") (class "Default")
      (node (ref "U4") (pin "11") (pinfunction "O_11") (pintype "output"))
      (node (ref "U4") (pin "4") (pinfunction "I0_4") (pintype "input"))
    )
    (net (code "48") (name "Net-(U5A-I)") (class "Default")
      (node (ref "C3") (pin "2") (pinfunction "2_2") (pintype "passive"))
      (node (ref "R15") (pin "1") (pinfunction "1_1") (pintype "passive"))
      (node (ref "U5") (pin "2") (pinfunction "I_2") (pintype "input"))
    )
    (net (code "49") (name "Net-(U6-AO)") (class "Default")
      (node (ref "R18") (pin "2") (pinfunction "2_2") (pintype "passive"))
      (node (ref "SJ2") (pin "1") (pinfunction "1_1") (pintype "passive"))
      (node (ref "U6") (pin "6") (pinfunction "AO_6") (pintype "bidirectional"))
    )
    (net (code "50") (name "Net-(U6-SCL)") (class "Default")
      (node (ref "R20") (pin "1") (pinfunction "1_1") (pintype "passive"))
      (node (ref "U6") (pin "5") (pinfunction "SCL_5") (pintype "bidirectional"))
      (node (ref "U7") (pin "3") (pinfunction "SCL1_3") (pintype "input"))
    )
    (net (code "51") (name "Net-(U6-SDA)") (class "Default")
      (node (ref "R19") (pin "1") (pinfunction "1_1") (pintype "passive"))
      (node (ref "U6") (pin "4") (pinfunction "SDA_4") (pintype "bidirectional"))
      (node (ref "U7") (pin "2") (pinfunction "SDA1_2") (pintype "input"))
    )
    (net (code "52") (name "ONEWIRE") (class "Default")
      (node (ref "M1") (pin "J6.8") (pinfunction "PC0_J6.8") (pintype "bidirectional"))
      (node (ref "R24") (pin "1") (pinfunction "1_1") (pintype "passive"))
      (node (ref "TEMP") (pin "2") (pinfunction "S_2") (pintype "passive"))
    )
    (net (code "53") (name "SCL") (class "Default")
      (node (ref "DISPLAY") (pin "3") (pinfunction "S_3") (pintype "passive"))
      (node (ref "M1") (pin "J2.2") (pinfunction "SCL/PC5_J2.2") (pintype "bidirectional"))
      (node (ref "R9") (pin "2") (pinfunction "2_2") (pintype "passive"))
      (node (ref "U7") (pin "6") (pinfunction "SCL2_6") (pintype "output"))
    )
    (net (code "54") (name "SDA") (class "Default")
      (node (ref "DISPLAY") (pin "4") (pinfunction "S_4") (pintype "passive"))
      (node (ref "M1") (pin "J2.1") (pinfunction "SDA/PC4_J2.1") (pintype "bidirectional"))
      (node (ref "R10") (pin "2") (pinfunction "2_2") (pintype "passive"))
      (node (ref "U7") (pin "7") (pinfunction "SDA2_7") (pintype "output"))
    )
    (net (code "55") (name "SH{slash}LD_SWITCH") (class "Default")
      (node (ref "J3") (pin "2") (pinfunction "S_2") (pintype "passive"))
      (node (ref "J4") (pin "2") (pinfunction "S_2") (pintype "passive"))
      (node (ref "U3") (pin "1") (pinfunction "SH/~{LD}_1") (pintype "input"))
    )
    (net (code "56") (name "SMC_LED") (class "Default")
      (node (ref "M1") (pin "J7.3") (pinfunction "PD7_J7.3") (pintype "bidirectional"))
      (node (ref "OK1") (pin "4") (pinfunction "COL_4") (pintype "passive"))
    )
    (net (code "57") (name "SMC_SW") (class "Default")
      (node (ref "M1") (pin "J7.2") (pinfunction "PB0_J7.2") (pintype "bidirectional"))
      (node (ref "R4") (pin "2") (pinfunction "2_2") (pintype "passive"))
    )
    (net (code "58") (name "STARTLED") (class "Default")
      (node (ref "START") (pin "2") (pinfunction "S_2") (pintype "passive"))
      (node (ref "T3") (pin "C") (pinfunction "C_C") (pintype "passive"))
    )
    (net (code "59") (name "STARTLED_") (class "Default")
      (node (ref "M1") (pin "J7.5") (pinfunction "PD5/OC0B_J7.5") (pintype "bidirectional"))
      (node (ref "R2") (pin "2") (pinfunction "2_2") (pintype "passive"))
    )
    (net (code "60") (name "STARTSW") (class "Default")
      (node (ref "M1") (pin "J7.6") (pinfunction "PD4_J7.6") (pintype "bidirectional"))
      (node (ref "START") (pin "4") (pinfunction "S_4") (pintype "passive"))
    )
    (net (code "61") (name "STOPLED") (class "Default")
      (node (ref "STOP") (pin "2") (pinfunction "S_2") (pintype "passive"))
      (node (ref "T4") (pin "C") (pinfunction "C_C") (pintype "passive"))
    )
    (net (code "62") (name "STOPLED_") (class "Default")
      (node (ref "M1") (pin "J7.4") (pinfunction "PD6/OC0A_J7.4") (pintype "bidirectional"))
      (node (ref "R3") (pin "2") (pinfunction "2_2") (pintype "passive"))
    )
    (net (code "63") (name "STOPSW") (class "Default")
      (node (ref "M1") (pin "J7.7") (pinfunction "PD3/INT1_J7.7") (pintype "bidirectional"))
      (node (ref "STOP") (pin "4") (pinfunction "S_4") (pintype "passive"))
    )
    (net (code "64") (name "unconnected-(F2-Pad1B)") (class "Default")
      (node (ref "F2") (pin "1B") (pinfunction "1B_1B") (pintype "passive"))
    )
    (net (code "65") (name "unconnected-(F2-Pad2B)") (class "Default")
      (node (ref "F2") (pin "2B") (pinfunction "2B_2B") (pintype "passive"))
    )
    (net (code "66") (name "unconnected-(M1-ADC7-PadJ3.3)") (class "Default")
      (node (ref "M1") (pin "J3.3") (pinfunction "ADC7_J3.3") (pintype "bidirectional"))
    )
    (net (code "67") (name "unconnected-(M1-MISO{slash}PB4-PadJ6.10)") (class "Default")
      (node (ref "M1") (pin "J6.10") (pinfunction "MISO/PB4_J6.10") (pintype "bidirectional"))
    )
    (net (code "68") (name "unconnected-(M1-PD0{slash}RX-PadJ7.11)") (class "Default")
      (node (ref "M1") (pin "J7.11") (pinfunction "PD0/RX_J7.11") (pintype "bidirectional"))
    )
    (net (code "69") (name "unconnected-(M1-PD1{slash}TX-PadJ7.12)") (class "Default")
      (node (ref "M1") (pin "J7.12") (pinfunction "PD1/TX_J7.12") (pintype "bidirectional"))
    )
    (net (code "70") (name "unconnected-(M1-P_CTS-PadJ1.5)") (class "Default")
      (node (ref "M1") (pin "J1.5") (pinfunction "P_CTS_J1.5") (pintype "bidirectional"))
    )
    (net (code "71") (name "unconnected-(M1-P_DTR-PadJ1.1)") (class "Default")
      (node (ref "M1") (pin "J1.1") (pinfunction "P_DTR_J1.1") (pintype "bidirectional"))
    )
    (net (code "72") (name "unconnected-(M1-P_RXD-PadJ1.2)") (class "Default")
      (node (ref "M1") (pin "J1.2") (pinfunction "P_RXD_J1.2") (pintype "bidirectional"))
    )
    (net (code "73") (name "unconnected-(M1-P_TXD-PadJ1.3)") (class "Default")
      (node (ref "M1") (pin "J1.3") (pinfunction "P_TXD_J1.3") (pintype "bidirectional"))
    )
    (net (code "74") (name "unconnected-(M1-RST.1-PadJ6.3)") (class "Default")
      (node (ref "M1") (pin "J6.3") (pinfunction "RST.1_J6.3") (pintype "bidirectional"))
    )
    (net (code "75") (name "unconnected-(M1-RST.2-PadJ7.10)") (class "Default")
      (node (ref "M1") (pin "J7.10") (pinfunction "RST.2_J7.10") (pintype "bidirectional"))
    )
    (net (code "76") (name "unconnected-(M1-SCK{slash}PB5-PadJ6.9)") (class "Default")
      (node (ref "M1") (pin "J6.9") (pinfunction "SCK/PB5_J6.9") (pintype "bidirectional"))
    )
    (net (code "77") (name "unconnected-(U1A-QA-Pad3)") (class "Default")
      (node (ref "U1") (pin "3") (pinfunction "QA_3") (pintype "output"))
    )
    (net (code "78") (name "unconnected-(U1A-QB-Pad4)") (class "Default")
      (node (ref "U1") (pin "4") (pinfunction "QB_4") (pintype "output"))
    )
    (net (code "79") (name "unconnected-(U1A-QD-Pad6)") (class "Default")
      (node (ref "U1") (pin "6") (pinfunction "QD_6") (pintype "output"))
    )
    (net (code "80") (name "unconnected-(U1A-QE-Pad10)") (class "Default")
      (node (ref "U1") (pin "10") (pinfunction "QE_10") (pintype "output"))
    )
    (net (code "81") (name "unconnected-(U1A-QF-Pad11)") (class "Default")
      (node (ref "U1") (pin "11") (pinfunction "QF_11") (pintype "output"))
    )
    (net (code "82") (name "unconnected-(U1A-QG-Pad12)") (class "Default")
      (node (ref "U1") (pin "12") (pinfunction "QG_12") (pintype "output"))
    )
    (net (code "83") (name "unconnected-(U2A-QA-Pad3)") (class "Default")
      (node (ref "U2") (pin "3") (pinfunction "QA_3") (pintype "output"))
    )
    (net (code "84") (name "unconnected-(U2A-QB-Pad4)") (class "Default")
      (node (ref "U2") (pin "4") (pinfunction "QB_4") (pintype "output"))
    )
    (net (code "85") (name "unconnected-(U2A-QC-Pad5)") (class "Default")
      (node (ref "U2") (pin "5") (pinfunction "QC_5") (pintype "output"))
    )
    (net (code "86") (name "unconnected-(U2A-QD-Pad6)") (class "Default")
      (node (ref "U2") (pin "6") (pinfunction "QD_6") (pintype "output"))
    )
    (net (code "87") (name "unconnected-(U2A-QF-Pad11)") (class "Default")
      (node (ref "U2") (pin "11") (pinfunction "QF_11") (pintype "output"))
    )
    (net (code "88") (name "unconnected-(U2A-QG-Pad12)") (class "Default")
      (node (ref "U2") (pin "12") (pinfunction "QG_12") (pintype "output"))
    )
    (net (code "89") (name "unconnected-(U2A-QH-Pad13)") (class "Default")
      (node (ref "U2") (pin "13") (pinfunction "QH_13") (pintype "output"))
    )
    (net (code "90") (name "unconnected-(U3A-~{QH}-Pad7)") (class "Default")
      (node (ref "U3") (pin "7") (pinfunction "~{QH}_7") (pintype "output"))
    )
  )
)
